# 40106PolyClock.net
KiCad netlist of a schematic drawn in EAGLE
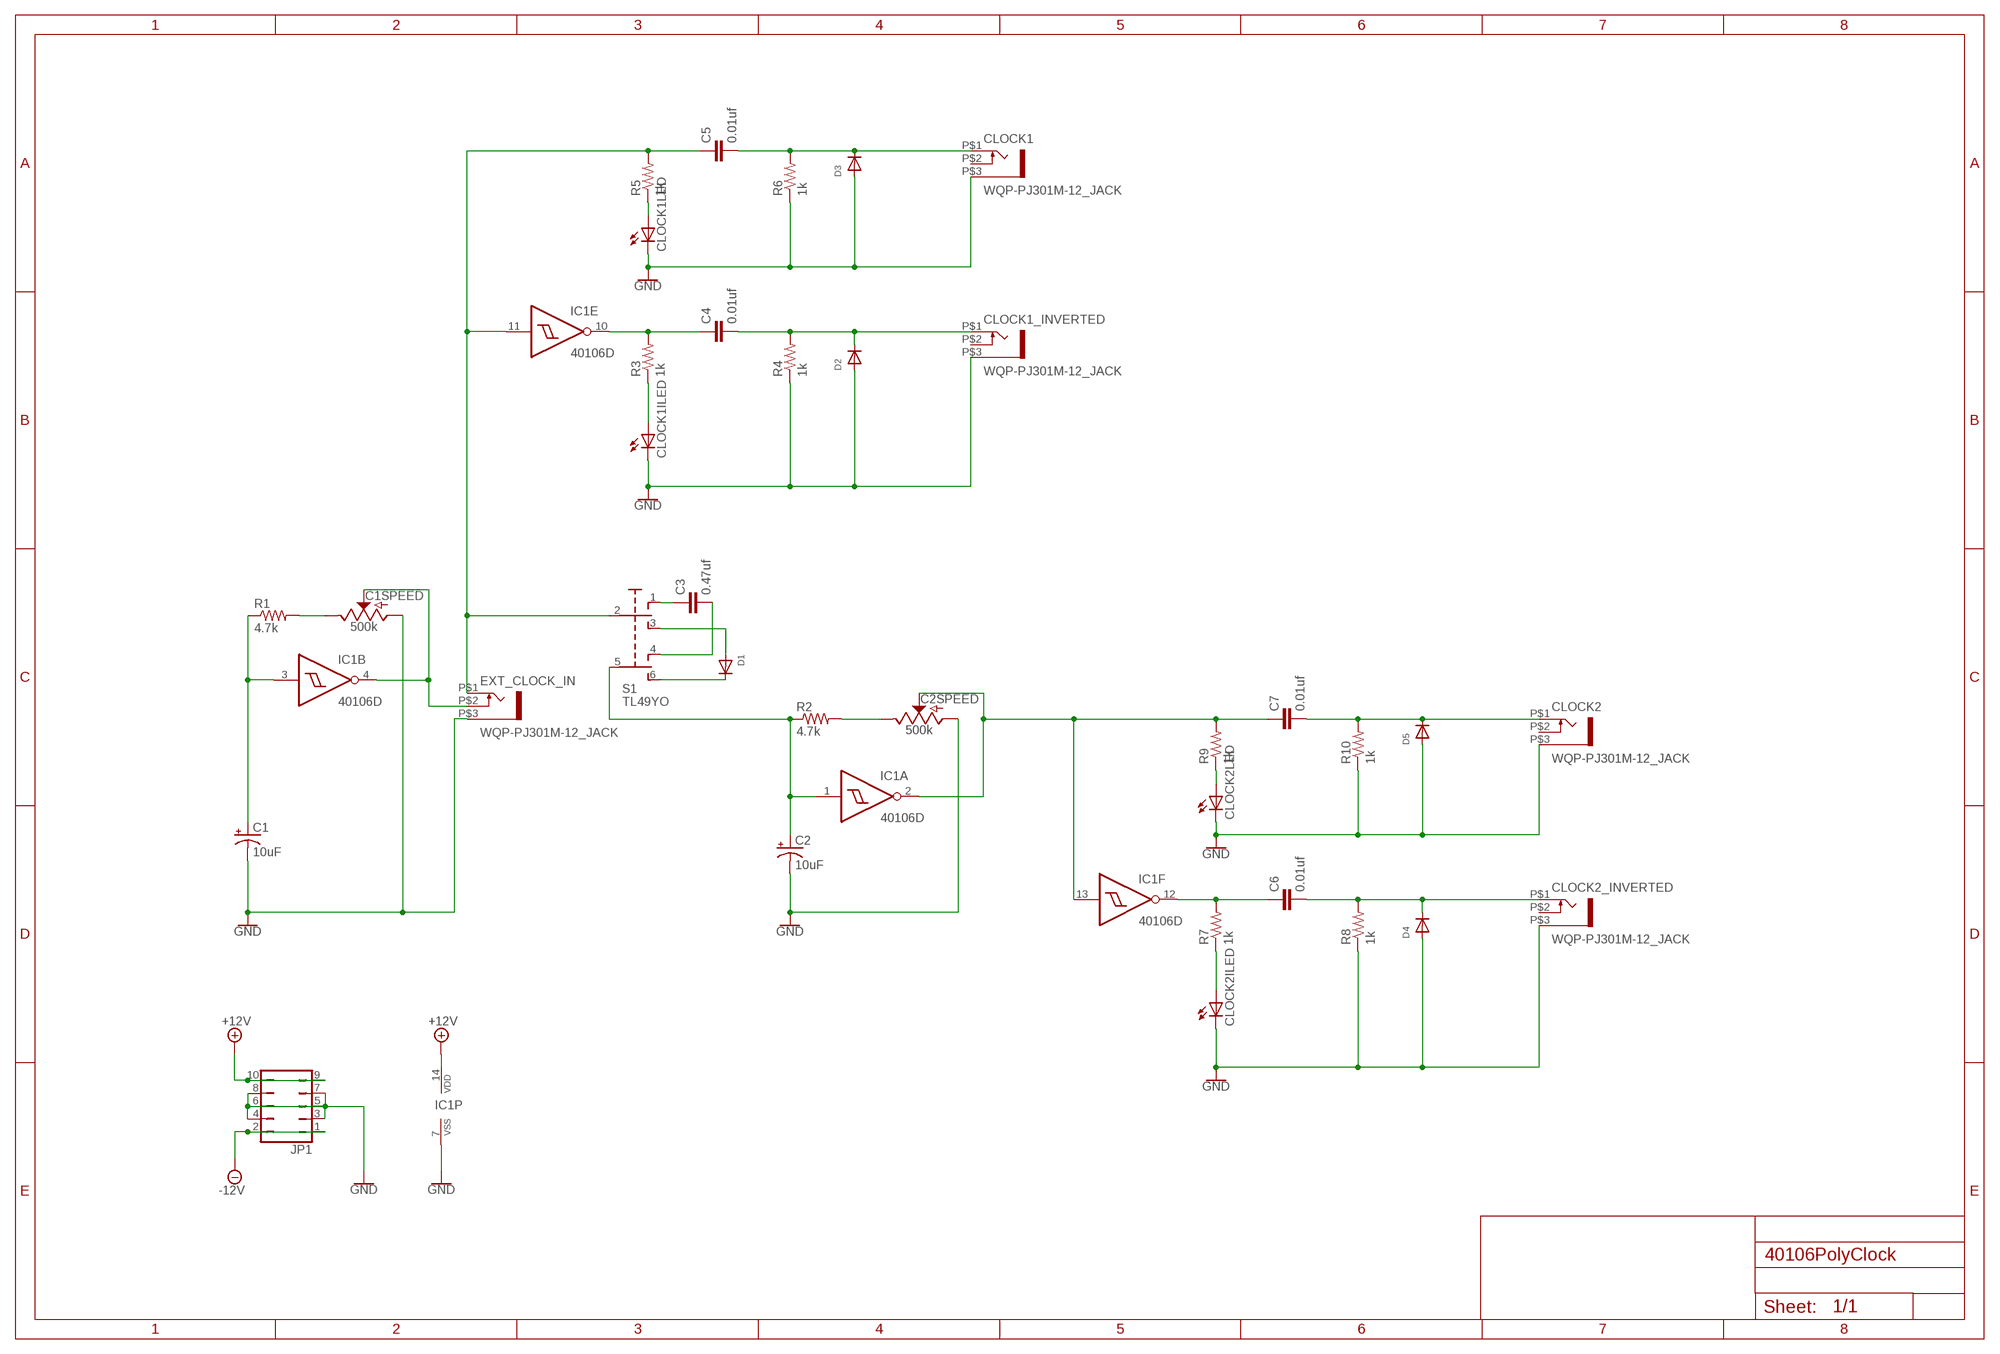
[diagram p0: schematic, sheet 1]

(export (version "E")
  (design (tool "Eeschema 10.0.6"))
  (components
    (comp (ref "C1")
      (value "10uF")
      (footprint "eagle-import:0603-POLAR")
      (libsource (lib "eagle-import") (part "10UF-POLAR-0603-6.3V-20%(TANT)"))
    )
    (comp (ref "C1SPEED")
      (value "500k")
      (footprint "eagle-import:POT-PTH-ALPS-KIT")
      (libsource (lib "eagle-import") (part "POTENTIOMETER-PTH-9MM-1/20W-20%-KIT"))
    )
    (comp (ref "C2")
      (value "10uF")
      (footprint "eagle-import:0603-POLAR")
      (libsource (lib "eagle-import") (part "10UF-POLAR-0603-6.3V-20%(TANT)"))
    )
    (comp (ref "C2SPEED")
      (value "500k")
      (footprint "eagle-import:POT-PTH-ALPS-KIT")
      (libsource (lib "eagle-import") (part "POTENTIOMETER-PTH-9MM-1/20W-20%-KIT"))
    )
    (comp (ref "C3")
      (value "0.47uf")
      (footprint "eagle-import:C1206")
      (libsource (lib "eagle-import") (part "C-EUC1206"))
    )
    (comp (ref "C4")
      (value "0.01uf")
      (footprint "eagle-import:C1206")
      (libsource (lib "eagle-import") (part "C-EUC1206"))
    )
    (comp (ref "C5")
      (value "0.01uf")
      (footprint "eagle-import:C1206")
      (libsource (lib "eagle-import") (part "C-EUC1206"))
    )
    (comp (ref "C6")
      (value "0.01uf")
      (footprint "eagle-import:C1206")
      (libsource (lib "eagle-import") (part "C-EUC1206"))
    )
    (comp (ref "C7")
      (value "0.01uf")
      (footprint "eagle-import:C1206")
      (libsource (lib "eagle-import") (part "C-EUC1206"))
    )
    (comp (ref "CLOCK1")
      (value "WQP-PJ301M-12_JACK")
      (footprint "eagle-import:WQP-PJ301M-12_JACK")
      (libsource (lib "eagle-import") (part "WQP-PJ301M-12_JACK"))
    )
    (comp (ref "CLOCK1ILED")
      (value "LED5MM")
      (footprint "eagle-import:LED5MM")
      (libsource (lib "eagle-import") (part "LED5MM"))
    )
    (comp (ref "CLOCK1LED")
      (value "LED5MM")
      (footprint "eagle-import:LED5MM")
      (libsource (lib "eagle-import") (part "LED5MM"))
    )
    (comp (ref "CLOCK1_INVERTED")
      (value "WQP-PJ301M-12_JACK")
      (footprint "eagle-import:WQP-PJ301M-12_JACK")
      (libsource (lib "eagle-import") (part "WQP-PJ301M-12_JACK"))
    )
    (comp (ref "CLOCK2")
      (value "WQP-PJ301M-12_JACK")
      (footprint "eagle-import:WQP-PJ301M-12_JACK")
      (libsource (lib "eagle-import") (part "WQP-PJ301M-12_JACK"))
    )
    (comp (ref "CLOCK2ILED")
      (value "LED5MM")
      (footprint "eagle-import:LED5MM")
      (libsource (lib "eagle-import") (part "LED5MM"))
    )
    (comp (ref "CLOCK2LED")
      (value "LED5MM")
      (footprint "eagle-import:LED5MM")
      (libsource (lib "eagle-import") (part "LED5MM"))
    )
    (comp (ref "CLOCK2_INVERTED")
      (value "WQP-PJ301M-12_JACK")
      (footprint "eagle-import:WQP-PJ301M-12_JACK")
      (libsource (lib "eagle-import") (part "WQP-PJ301M-12_JACK"))
    )
    (comp (ref "D1")
      (value "DIODESOD-123")
      (footprint "eagle-import:SOD-123")
      (libsource (lib "eagle-import") (part "DIODESOD-123"))
    )
    (comp (ref "D2")
      (value "DIODESOD-123")
      (footprint "eagle-import:SOD-123")
      (libsource (lib "eagle-import") (part "DIODESOD-123"))
    )
    (comp (ref "D3")
      (value "DIODESOD-123")
      (footprint "eagle-import:SOD-123")
      (libsource (lib "eagle-import") (part "DIODESOD-123"))
    )
    (comp (ref "D4")
      (value "DIODESOD-123")
      (footprint "eagle-import:SOD-123")
      (libsource (lib "eagle-import") (part "DIODESOD-123"))
    )
    (comp (ref "D5")
      (value "DIODESOD-123")
      (footprint "eagle-import:SOD-123")
      (libsource (lib "eagle-import") (part "DIODESOD-123"))
    )
    (comp (ref "EXT_CLOCK_IN")
      (value "WQP-PJ301M-12_JACK")
      (footprint "eagle-import:WQP-PJ301M-12_JACK")
      (libsource (lib "eagle-import") (part "WQP-PJ301M-12_JACK"))
    )
    (comp (ref "IC1")
      (value "40106D")
      (footprint "eagle-import:SO14")
      (libsource (lib "eagle-import") (part "40106D"))
    )
    (comp (ref "JP1")
      (value "JP5Q")
      (footprint "eagle-import:JP5Q")
      (libsource (lib "eagle-import") (part "JP5Q"))
    )
    (comp (ref "R1")
      (value "4.7k")
      (footprint "eagle-import:R1206")
      (libsource (lib "eagle-import") (part "R-US_R1206"))
    )
    (comp (ref "R2")
      (value "4.7k")
      (footprint "eagle-import:R1206")
      (libsource (lib "eagle-import") (part "R-US_R1206"))
    )
    (comp (ref "R3")
      (value "1k")
      (footprint "eagle-import:R1206")
      (libsource (lib "eagle-import") (part "R-US_R1206"))
    )
    (comp (ref "R4")
      (value "1k")
      (footprint "eagle-import:R1206")
      (libsource (lib "eagle-import") (part "R-US_R1206"))
    )
    (comp (ref "R5")
      (value "1k")
      (footprint "eagle-import:R1206")
      (libsource (lib "eagle-import") (part "R-US_R1206"))
    )
    (comp (ref "R6")
      (value "1k")
      (footprint "eagle-import:R1206")
      (libsource (lib "eagle-import") (part "R-US_R1206"))
    )
    (comp (ref "R7")
      (value "1k")
      (footprint "eagle-import:R1206")
      (libsource (lib "eagle-import") (part "R-US_R1206"))
    )
    (comp (ref "R8")
      (value "1k")
      (footprint "eagle-import:R1206")
      (libsource (lib "eagle-import") (part "R-US_R1206"))
    )
    (comp (ref "R9")
      (value "1k")
      (footprint "eagle-import:R1206")
      (libsource (lib "eagle-import") (part "R-US_R1206"))
    )
    (comp (ref "R10")
      (value "1k")
      (footprint "eagle-import:R1206")
      (libsource (lib "eagle-import") (part "R-US_R1206"))
    )
    (comp (ref "S1")
      (value "TL49YO")
      (footprint "eagle-import:TL4XYO")
      (libsource (lib "eagle-import") (part "TL49YO"))
    )
  )
  (nets
    (net (code "1") (name "+12V") (class "Default")
      (node (ref "IC1") (pin "14") (pinfunction "VDD_14") (pintype "power_in"))
      (node (ref "JP1") (pin "10") (pinfunction "10_10") (pintype "passive"))
      (node (ref "JP1") (pin "9") (pinfunction "9_9") (pintype "passive"))
    )
    (net (code "2") (name "-12V") (class "Default")
      (node (ref "JP1") (pin "1") (pinfunction "1_1") (pintype "passive"))
      (node (ref "JP1") (pin "2") (pinfunction "2_2") (pintype "passive"))
    )
    (net (code "3") (name "GND") (class "Default")
      (node (ref "C1") (pin "-") (pinfunction "-_-") (pintype "passive"))
      (node (ref "C1SPEED") (pin "P$3") (pinfunction "A_P$3") (pintype "passive"))
      (node (ref "C2") (pin "-") (pinfunction "-_-") (pintype "passive"))
      (node (ref "C2SPEED") (pin "P$3") (pinfunction "A_P$3") (pintype "passive"))
      (node (ref "CLOCK1") (pin "P$3") (pinfunction "1_P$3") (pintype "passive"))
      (node (ref "CLOCK1ILED") (pin "K") (pinfunction "C_K") (pintype "passive"))
      (node (ref "CLOCK1LED") (pin "K") (pinfunction "C_K") (pintype "passive"))
      (node (ref "CLOCK1_INVERTED") (pin "P$3") (pinfunction "1_P$3") (pintype "passive"))
      (node (ref "CLOCK2") (pin "P$3") (pinfunction "1_P$3") (pintype "passive"))
      (node (ref "CLOCK2ILED") (pin "K") (pinfunction "C_K") (pintype "passive"))
      (node (ref "CLOCK2LED") (pin "K") (pinfunction "C_K") (pintype "passive"))
      (node (ref "CLOCK2_INVERTED") (pin "P$3") (pinfunction "1_P$3") (pintype "passive"))
      (node (ref "D2") (pin "A") (pinfunction "A_A") (pintype "passive"))
      (node (ref "D3") (pin "A") (pinfunction "A_A") (pintype "passive"))
      (node (ref "D4") (pin "A") (pinfunction "A_A") (pintype "passive"))
      (node (ref "D5") (pin "A") (pinfunction "A_A") (pintype "passive"))
      (node (ref "EXT_CLOCK_IN") (pin "P$3") (pinfunction "1_P$3") (pintype "passive"))
      (node (ref "IC1") (pin "7") (pinfunction "VSS_7") (pintype "power_in"))
      (node (ref "JP1") (pin "3") (pinfunction "3_3") (pintype "passive"))
      (node (ref "JP1") (pin "4") (pinfunction "4_4") (pintype "passive"))
      (node (ref "JP1") (pin "5") (pinfunction "5_5") (pintype "passive"))
      (node (ref "JP1") (pin "6") (pinfunction "6_6") (pintype "passive"))
      (node (ref "JP1") (pin "7") (pinfunction "7_7") (pintype "passive"))
      (node (ref "JP1") (pin "8") (pinfunction "8_8") (pintype "passive"))
      (node (ref "R10") (pin "1") (pinfunction "1_1") (pintype "passive"))
      (node (ref "R4") (pin "1") (pinfunction "1_1") (pintype "passive"))
      (node (ref "R6") (pin "1") (pinfunction "1_1") (pintype "passive"))
      (node (ref "R8") (pin "1") (pinfunction "1_1") (pintype "passive"))
    )
    (net (code "4") (name "Net-(C1SPEED-E)") (class "Default")
      (node (ref "C1SPEED") (pin "P$1") (pinfunction "E_P$1") (pintype "passive"))
      (node (ref "R1") (pin "2") (pinfunction "2_2") (pintype "passive"))
    )
    (net (code "5") (name "Net-(C1SPEED-S)") (class "Default")
      (node (ref "C1SPEED") (pin "P$2") (pinfunction "S_P$2") (pintype "passive"))
      (node (ref "EXT_CLOCK_IN") (pin "P$2") (pinfunction "3_P$2") (pintype "passive"))
      (node (ref "IC1") (pin "4") (pinfunction "O_4") (pintype "output"))
    )
    (net (code "6") (name "Net-(C2SPEED-E)") (class "Default")
      (node (ref "C2SPEED") (pin "P$1") (pinfunction "E_P$1") (pintype "passive"))
      (node (ref "R2") (pin "2") (pinfunction "2_2") (pintype "passive"))
    )
    (net (code "7") (name "Net-(C2SPEED-S)") (class "Default")
      (node (ref "C2SPEED") (pin "P$2") (pinfunction "S_P$2") (pintype "passive"))
      (node (ref "C7") (pin "1") (pinfunction "1_1") (pintype "passive"))
      (node (ref "IC1") (pin "13") (pinfunction "I_13") (pintype "input"))
      (node (ref "IC1") (pin "2") (pinfunction "O_2") (pintype "output"))
      (node (ref "R9") (pin "2") (pinfunction "2_2") (pintype "passive"))
    )
    (net (code "8") (name "Net-(CLOCK1-2)") (class "Default")
      (node (ref "C5") (pin "2") (pinfunction "2_2") (pintype "passive"))
      (node (ref "CLOCK1") (pin "P$1") (pinfunction "2_P$1") (pintype "passive"))
      (node (ref "D3") (pin "C") (pinfunction "C_C") (pintype "passive"))
      (node (ref "R6") (pin "2") (pinfunction "2_2") (pintype "passive"))
    )
    (net (code "9") (name "Net-(CLOCK1ILED-PadA)") (class "Default")
      (node (ref "CLOCK1ILED") (pin "A") (pinfunction "A_A") (pintype "passive"))
      (node (ref "R3") (pin "1") (pinfunction "1_1") (pintype "passive"))
    )
    (net (code "10") (name "Net-(CLOCK1LED-PadA)") (class "Default")
      (node (ref "CLOCK1LED") (pin "A") (pinfunction "A_A") (pintype "passive"))
      (node (ref "R5") (pin "1") (pinfunction "1_1") (pintype "passive"))
    )
    (net (code "11") (name "Net-(CLOCK1_INVERTED-2)") (class "Default")
      (node (ref "C4") (pin "2") (pinfunction "2_2") (pintype "passive"))
      (node (ref "CLOCK1_INVERTED") (pin "P$1") (pinfunction "2_P$1") (pintype "passive"))
      (node (ref "D2") (pin "C") (pinfunction "C_C") (pintype "passive"))
      (node (ref "R4") (pin "2") (pinfunction "2_2") (pintype "passive"))
    )
    (net (code "12") (name "Net-(CLOCK2-2)") (class "Default")
      (node (ref "C7") (pin "2") (pinfunction "2_2") (pintype "passive"))
      (node (ref "CLOCK2") (pin "P$1") (pinfunction "2_P$1") (pintype "passive"))
      (node (ref "D5") (pin "C") (pinfunction "C_C") (pintype "passive"))
      (node (ref "R10") (pin "2") (pinfunction "2_2") (pintype "passive"))
    )
    (net (code "13") (name "Net-(CLOCK2ILED-PadA)") (class "Default")
      (node (ref "CLOCK2ILED") (pin "A") (pinfunction "A_A") (pintype "passive"))
      (node (ref "R7") (pin "1") (pinfunction "1_1") (pintype "passive"))
    )
    (net (code "14") (name "Net-(CLOCK2LED-PadA)") (class "Default")
      (node (ref "CLOCK2LED") (pin "A") (pinfunction "A_A") (pintype "passive"))
      (node (ref "R9") (pin "1") (pinfunction "1_1") (pintype "passive"))
    )
    (net (code "15") (name "Net-(CLOCK2_INVERTED-2)") (class "Default")
      (node (ref "C6") (pin "2") (pinfunction "2_2") (pintype "passive"))
      (node (ref "CLOCK2_INVERTED") (pin "P$1") (pinfunction "2_P$1") (pintype "passive"))
      (node (ref "D4") (pin "C") (pinfunction "C_C") (pintype "passive"))
      (node (ref "R8") (pin "2") (pinfunction "2_2") (pintype "passive"))
    )
    (net (code "16") (name "Net-(EXT_CLOCK_IN-2)") (class "Default")
      (node (ref "C5") (pin "1") (pinfunction "1_1") (pintype "passive"))
      (node (ref "EXT_CLOCK_IN") (pin "P$1") (pinfunction "2_P$1") (pintype "passive"))
      (node (ref "IC1") (pin "11") (pinfunction "I_11") (pintype "input"))
      (node (ref "R5") (pin "2") (pinfunction "2_2") (pintype "passive"))
      (node (ref "S1") (pin "2") (pinfunction "P_2") (pintype "passive"))
    )
    (net (code "17") (name "Net-(IC1A-I)") (class "Default")
      (node (ref "C2") (pin "+") (pinfunction "+_+") (pintype "passive"))
      (node (ref "IC1") (pin "1") (pinfunction "I_1") (pintype "input"))
      (node (ref "R2") (pin "1") (pinfunction "1_1") (pintype "passive"))
      (node (ref "S1") (pin "5") (pinfunction "P1_5") (pintype "passive"))
    )
    (net (code "18") (name "Net-(IC1B-I)") (class "Default")
      (node (ref "C1") (pin "+") (pinfunction "+_+") (pintype "passive"))
      (node (ref "IC1") (pin "3") (pinfunction "I_3") (pintype "input"))
      (node (ref "R1") (pin "1") (pinfunction "1_1") (pintype "passive"))
    )
    (net (code "19") (name "Net-(IC1E-O)") (class "Default")
      (node (ref "C4") (pin "1") (pinfunction "1_1") (pintype "passive"))
      (node (ref "IC1") (pin "10") (pinfunction "O_10") (pintype "output"))
      (node (ref "R3") (pin "2") (pinfunction "2_2") (pintype "passive"))
    )
    (net (code "20") (name "Net-(IC1F-O)") (class "Default")
      (node (ref "C6") (pin "1") (pinfunction "1_1") (pintype "passive"))
      (node (ref "IC1") (pin "12") (pinfunction "O_12") (pintype "output"))
      (node (ref "R7") (pin "2") (pinfunction "2_2") (pintype "passive"))
    )
    (net (code "21") (name "Net-(S1-O)") (class "Default")
      (node (ref "C3") (pin "1") (pinfunction "1_1") (pintype "passive"))
      (node (ref "S1") (pin "1") (pinfunction "O_1") (pintype "passive"))
    )
    (net (code "22") (name "Net-(S1-O1)") (class "Default")
      (node (ref "C3") (pin "2") (pinfunction "2_2") (pintype "passive"))
      (node (ref "S1") (pin "4") (pinfunction "O1_4") (pintype "passive"))
    )
    (net (code "23") (name "Net-(S1-S)") (class "Default")
      (node (ref "D1") (pin "A") (pinfunction "A_A") (pintype "passive"))
      (node (ref "S1") (pin "3") (pinfunction "S_3") (pintype "passive"))
    )
    (net (code "24") (name "Net-(S1-S1)") (class "Default")
      (node (ref "D1") (pin "C") (pinfunction "C_C") (pintype "passive"))
      (node (ref "S1") (pin "6") (pinfunction "S1_6") (pintype "passive"))
    )
    (net (code "25") (name "unconnected-(CLOCK1-3-PadP$2)") (class "Default")
      (node (ref "CLOCK1") (pin "P$2") (pinfunction "3_P$2") (pintype "passive"))
    )
    (net (code "26") (name "unconnected-(CLOCK1_INVERTED-3-PadP$2)") (class "Default")
      (node (ref "CLOCK1_INVERTED") (pin "P$2") (pinfunction "3_P$2") (pintype "passive"))
    )
    (net (code "27") (name "unconnected-(CLOCK2-3-PadP$2)") (class "Default")
      (node (ref "CLOCK2") (pin "P$2") (pinfunction "3_P$2") (pintype "passive"))
    )
    (net (code "28") (name "unconnected-(CLOCK2_INVERTED-3-PadP$2)") (class "Default")
      (node (ref "CLOCK2_INVERTED") (pin "P$2") (pinfunction "3_P$2") (pintype "passive"))
    )
  )
)
